# MewPro-ver1_1.net
KiCad netlist of a schematic drawn in EAGLE
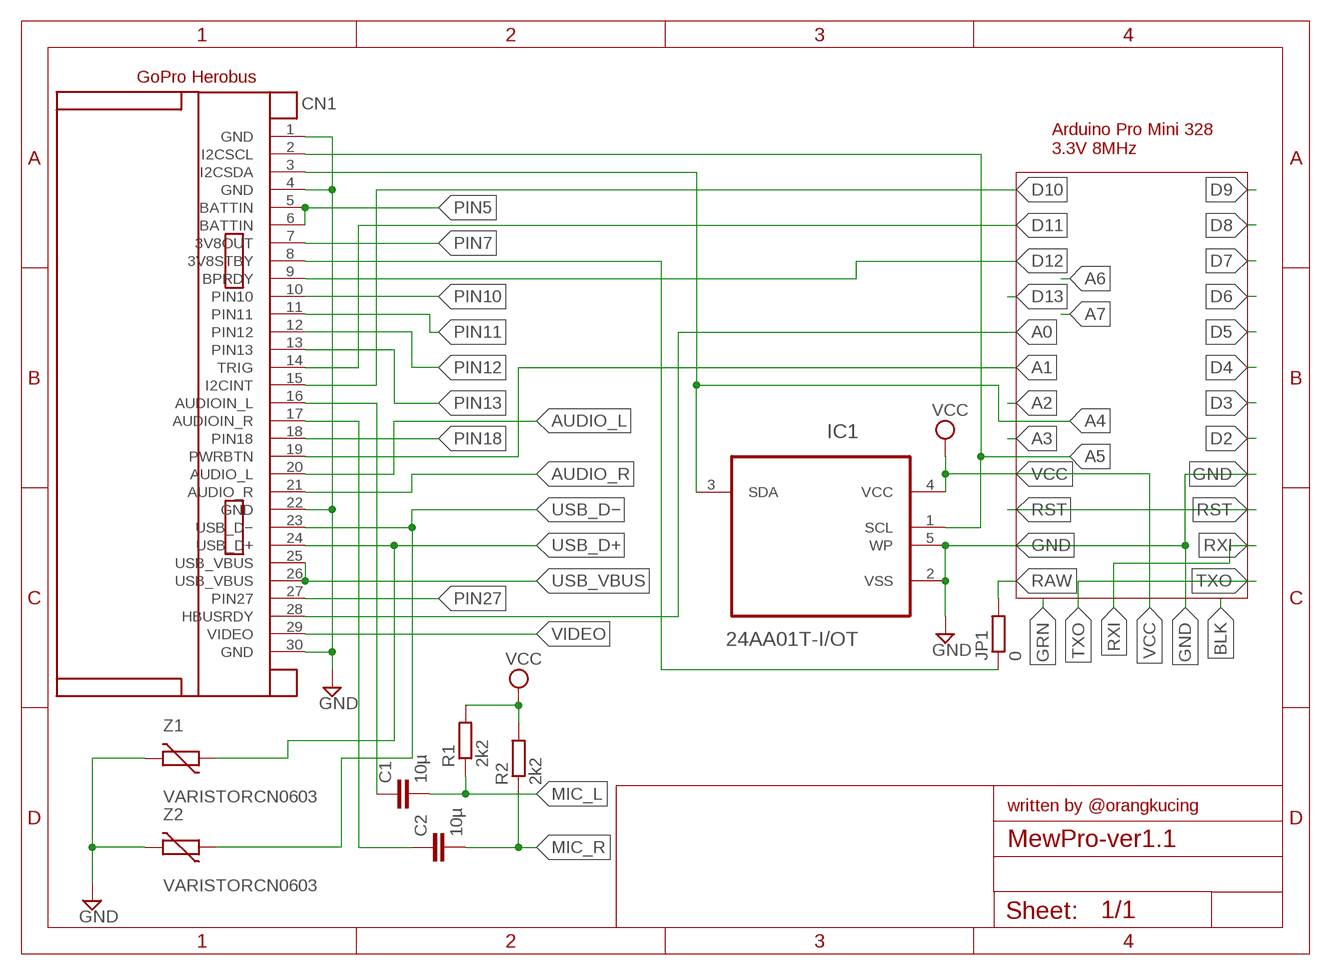
[diagram p0: schematic, sheet 1]

(export (version "E")
  (design (tool "Eeschema 10.0.6"))
  (components
    (comp (ref "C1")
      (value "10µ")
      (footprint "eagle-import:C0603")
      (libsource (lib "eagle-import") (part "C-EUC0603"))
    )
    (comp (ref "C2")
      (value "10µ")
      (footprint "eagle-import:C0603")
      (libsource (lib "eagle-import") (part "C-EUC0603"))
    )
    (comp (ref "CN1")
      (value "GOPRO-HEROBUS-CONNECTOR")
      (footprint "eagle-import:GOPRO_CONNECTOR")
      (libsource (lib "eagle-import") (part "GOPRO-HEROBUS-CONNECTOR"))
    )
    (comp (ref "IC1")
      (value "24AA01T-I/OT")
      (footprint "eagle-import:SOT95P270X145-5N")
      (libsource (lib "eagle-import") (part "24AA01T-I/OT"))
    )
    (comp (ref "JP1")
      (value "0")
      (footprint "eagle-import:R0805")
      (libsource (lib "eagle-import") (part "R-EU_R0805"))
    )
    (comp (ref "R1")
      (value "2k2")
      (footprint "eagle-import:R0603")
      (libsource (lib "eagle-import") (part "R-EU_R0603"))
    )
    (comp (ref "R2")
      (value "2k2")
      (footprint "eagle-import:R0603")
      (libsource (lib "eagle-import") (part "R-EU_R0603"))
    )
    (comp (ref "Z1")
      (value "VARISTORCN0603")
      (footprint "eagle-import:CT_CN0603")
      (libsource (lib "eagle-import") (part "VARISTORCN0603"))
    )
    (comp (ref "Z2")
      (value "VARISTORCN0603")
      (footprint "eagle-import:CT_CN0603")
      (libsource (lib "eagle-import") (part "VARISTORCN0603"))
    )
  )
  (nets
    (net (code "1") (name "A0") (class "Default")
      (node (ref "CN1") (pin "28") (pinfunction "HBUSRDY_28") (pintype "bidirectional"))
    )
    (net (code "2") (name "A1") (class "Default")
      (node (ref "CN1") (pin "19") (pinfunction "PWRBTN_19") (pintype "bidirectional"))
    )
    (net (code "5") (name "A4") (class "Default")
      (node (ref "CN1") (pin "3") (pinfunction "I2CSDA_3") (pintype "bidirectional"))
      (node (ref "IC1") (pin "3") (pinfunction "SDA_3") (pintype "bidirectional"))
    )
    (net (code "6") (name "A5") (class "Default")
      (node (ref "CN1") (pin "2") (pinfunction "I2CSCL_2") (pintype "bidirectional"))
      (node (ref "IC1") (pin "1") (pinfunction "SCL_1") (pintype "input"))
    )
    (net (code "9") (name "AUDIO_L") (class "Default")
      (node (ref "CN1") (pin "20") (pinfunction "AUDIO_L_20") (pintype "bidirectional"))
    )
    (net (code "10") (name "AUDIO_R") (class "Default")
      (node (ref "CN1") (pin "21") (pinfunction "AUDIO_R_21") (pintype "bidirectional"))
    )
    (net (code "20") (name "D10") (class "Default")
      (node (ref "CN1") (pin "15") (pinfunction "I2CINT_15") (pintype "bidirectional"))
    )
    (net (code "21") (name "D11") (class "Default")
      (node (ref "CN1") (pin "14") (pinfunction "TRIG_14") (pintype "bidirectional"))
    )
    (net (code "22") (name "D12") (class "Default")
      (node (ref "CN1") (pin "9") (pinfunction "BPRDY_9") (pintype "bidirectional"))
    )
    (net (code "24") (name "GND") (class "Default")
      (node (ref "CN1") (pin "1") (pinfunction "GND_1") (pintype "bidirectional"))
      (node (ref "CN1") (pin "22") (pinfunction "GND_22") (pintype "bidirectional"))
      (node (ref "CN1") (pin "30") (pinfunction "GND_30") (pintype "bidirectional"))
      (node (ref "CN1") (pin "4") (pinfunction "GND_4") (pintype "bidirectional"))
      (node (ref "IC1") (pin "2") (pinfunction "VSS_2") (pintype "passive"))
      (node (ref "IC1") (pin "5") (pinfunction "WP_5") (pintype "input"))
      (node (ref "Z1") (pin "2") (pinfunction "2_2") (pintype "passive"))
      (node (ref "Z2") (pin "2") (pinfunction "2_2") (pintype "passive"))
    )
    (net (code "26") (name "MIC_L") (class "Default")
      (node (ref "C1") (pin "2") (pinfunction "2_2") (pintype "passive"))
      (node (ref "R1") (pin "1") (pinfunction "1_1") (pintype "passive"))
    )
    (net (code "27") (name "MIC_R") (class "Default")
      (node (ref "C2") (pin "2") (pinfunction "2_2") (pintype "passive"))
      (node (ref "R2") (pin "1") (pinfunction "1_1") (pintype "passive"))
    )
    (net (code "28") (name "Net-(CN1-3V8STBY)") (class "Default")
      (node (ref "CN1") (pin "8") (pinfunction "3V8STBY_8") (pintype "bidirectional"))
      (node (ref "JP1") (pin "1") (pinfunction "1_1") (pintype "passive"))
    )
    (net (code "29") (name "Net-(CN1-AUDIOIN_L)") (class "Default")
      (node (ref "C1") (pin "1") (pinfunction "1_1") (pintype "passive"))
      (node (ref "CN1") (pin "16") (pinfunction "AUDIOIN_L_16") (pintype "bidirectional"))
    )
    (net (code "30") (name "Net-(CN1-AUDIOIN_R)") (class "Default")
      (node (ref "C2") (pin "1") (pinfunction "1_1") (pintype "passive"))
      (node (ref "CN1") (pin "17") (pinfunction "AUDIOIN_R_17") (pintype "bidirectional"))
    )
    (net (code "31") (name "PIN5") (class "Default")
      (node (ref "CN1") (pin "5") (pinfunction "BATTIN_5") (pintype "bidirectional"))
      (node (ref "CN1") (pin "6") (pinfunction "BATTIN_6") (pintype "bidirectional"))
    )
    (net (code "32") (name "PIN7") (class "Default")
      (node (ref "CN1") (pin "7") (pinfunction "3V8OUT_7") (pintype "bidirectional"))
    )
    (net (code "33") (name "PIN10") (class "Default")
      (node (ref "CN1") (pin "10") (pinfunction "PIN10_10") (pintype "bidirectional"))
    )
    (net (code "34") (name "PIN11") (class "Default")
      (node (ref "CN1") (pin "11") (pinfunction "PIN11_11") (pintype "bidirectional"))
    )
    (net (code "35") (name "PIN12") (class "Default")
      (node (ref "CN1") (pin "12") (pinfunction "PIN12_12") (pintype "bidirectional"))
    )
    (net (code "36") (name "PIN13") (class "Default")
      (node (ref "CN1") (pin "13") (pinfunction "PIN13_13") (pintype "bidirectional"))
    )
    (net (code "37") (name "PIN18") (class "Default")
      (node (ref "CN1") (pin "18") (pinfunction "PIN18_18") (pintype "bidirectional"))
    )
    (net (code "38") (name "PIN27") (class "Default")
      (node (ref "CN1") (pin "27") (pinfunction "PIN27_27") (pintype "bidirectional"))
    )
    (net (code "39") (name "RAW") (class "Default")
      (node (ref "JP1") (pin "2") (pinfunction "2_2") (pintype "passive"))
    )
    (net (code "43") (name "USB_D+") (class "Default")
      (node (ref "CN1") (pin "24") (pinfunction "USB_D+_24") (pintype "bidirectional"))
      (node (ref "Z1") (pin "1") (pinfunction "1_1") (pintype "passive"))
    )
    (net (code "44") (name "USB_D−") (class "Default")
      (node (ref "CN1") (pin "23") (pinfunction "USB_D−_23") (pintype "bidirectional"))
      (node (ref "Z2") (pin "1") (pinfunction "1_1") (pintype "passive"))
    )
    (net (code "45") (name "USB_VBUS") (class "Default")
      (node (ref "CN1") (pin "25") (pinfunction "USB_VBUS_25") (pintype "bidirectional"))
      (node (ref "CN1") (pin "26") (pinfunction "USB_VBUS_26") (pintype "bidirectional"))
    )
    (net (code "46") (name "VCC") (class "Default")
      (node (ref "IC1") (pin "4") (pinfunction "VCC_4") (pintype "power_in"))
      (node (ref "R1") (pin "2") (pinfunction "2_2") (pintype "passive"))
      (node (ref "R2") (pin "2") (pinfunction "2_2") (pintype "passive"))
    )
    (net (code "47") (name "VIDEO") (class "Default")
      (node (ref "CN1") (pin "29") (pinfunction "VIDEO_29") (pintype "bidirectional"))
    )
  )
)
